# device.net
KiCad netlist of a schematic drawn in Altium Designer
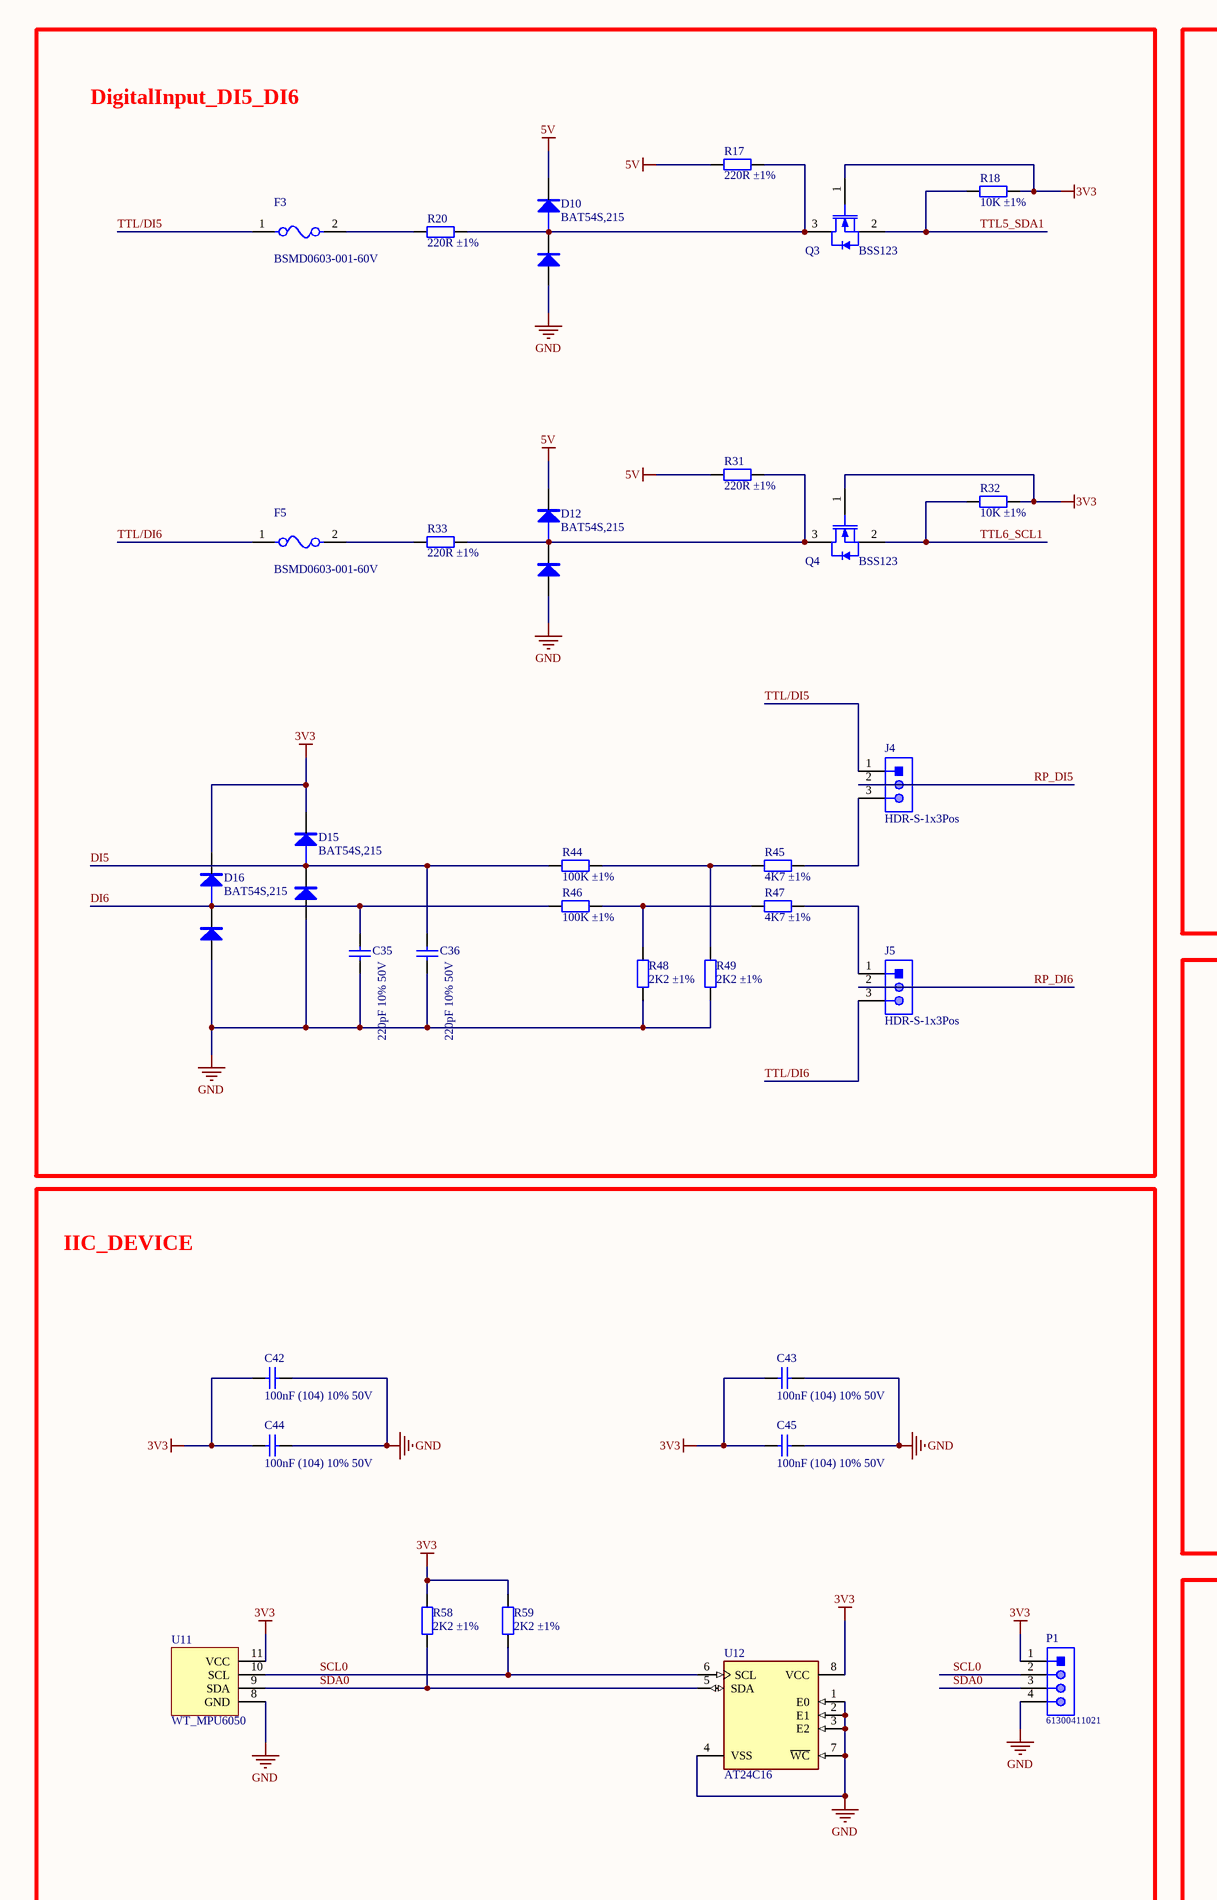
[diagram p0: device.SchDoc, left]
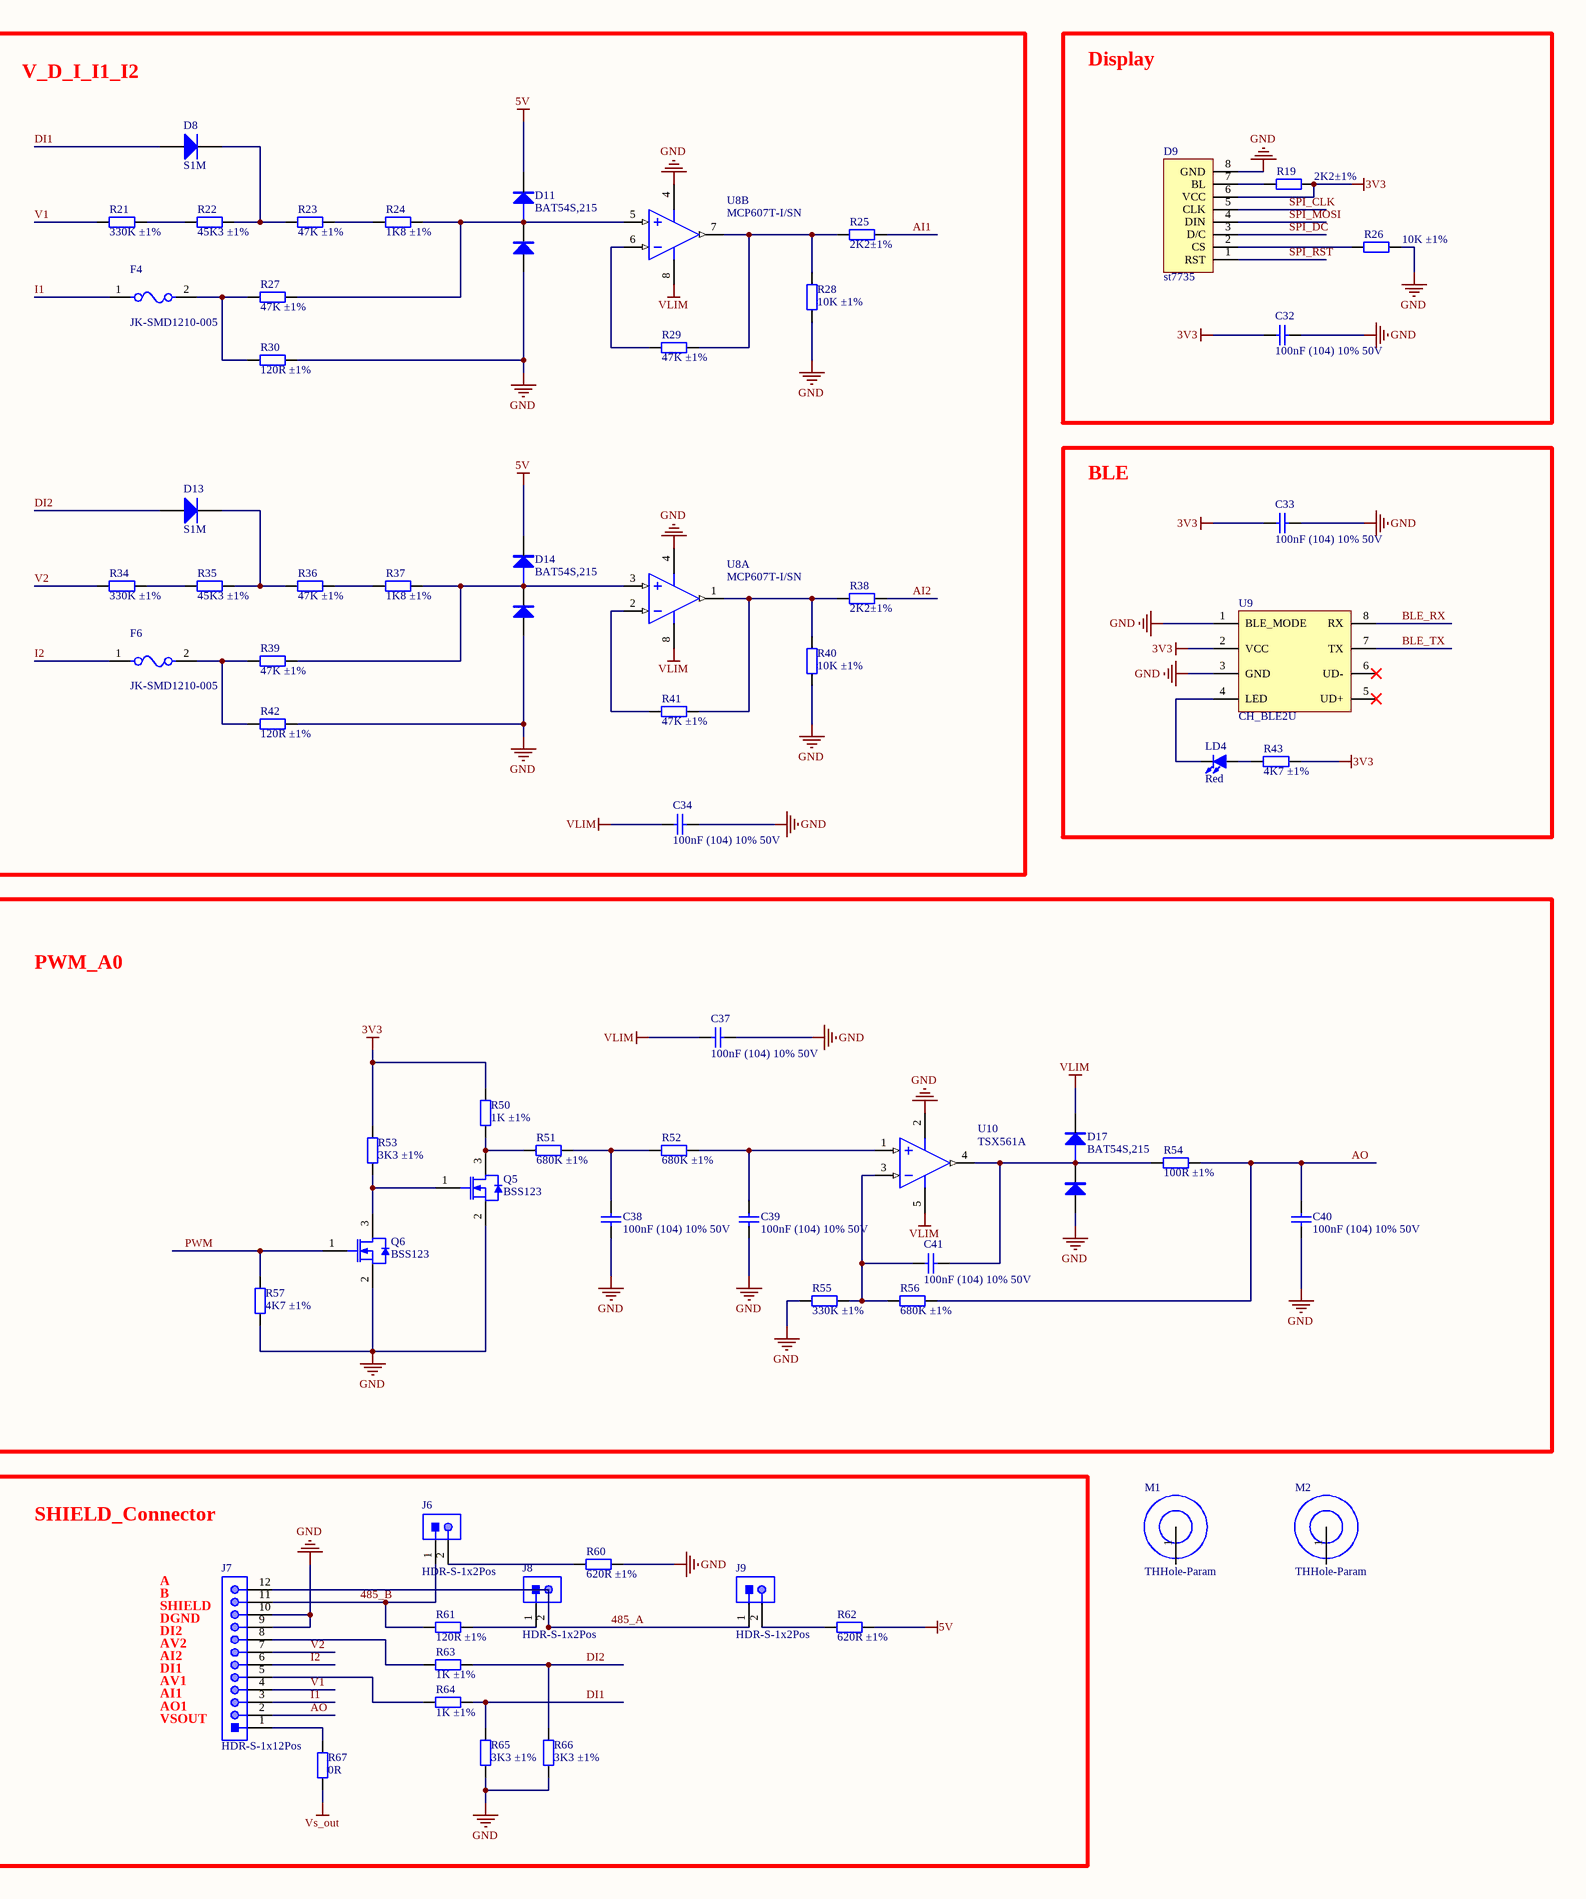
[diagram p1: device.SchDoc, right]

(export (version "E")
  (design (tool "Eeschema 10.0.6"))
  (components
    (comp (ref "C32")
      (value "100nF (104) 10% 50V")
      (footprint "0402_C")
      (description "贴片电容")
      (libsource (lib "aiskylab-02Cap-01Ceramics") (part "0402 100nF (104) 10% 16V"))
    )
    (comp (ref "C33")
      (value "100nF (104) 10% 50V")
      (footprint "0402_C")
      (description "贴片电容")
      (libsource (lib "aiskylab-02Cap-01Ceramics") (part "0402 100nF (104) 10% 16V"))
    )
    (comp (ref "C34")
      (value "100nF (104) 10% 50V")
      (footprint "0402_C")
      (description "贴片电容")
      (libsource (lib "aiskylab-02Cap-01Ceramics") (part "0402 100nF (104) 10% 16V"))
    )
    (comp (ref "C35")
      (value "220pF 10% 50V")
      (footprint "0402_C")
      (description "贴片电容")
      (libsource (lib "aiskylab-02Cap-01Ceramics") (part "0402 150pF (151) 10% 50V"))
    )
    (comp (ref "C36")
      (value "220pF 10% 50V")
      (footprint "0402_C")
      (description "贴片电容")
      (libsource (lib "aiskylab-02Cap-01Ceramics") (part "0402 150pF (151) 10% 50V"))
    )
    (comp (ref "C37")
      (value "100nF (104) 10% 50V")
      (footprint "0402_C")
      (description "贴片电容")
      (libsource (lib "aiskylab-02Cap-01Ceramics") (part "0402 100nF (104) 10% 16V"))
    )
    (comp (ref "C38")
      (value "100nF (104) 10% 50V")
      (footprint "0402_C")
      (description "贴片电容")
      (libsource (lib "aiskylab-02Cap-01Ceramics") (part "0402 100nF (104) 10% 16V"))
    )
    (comp (ref "C39")
      (value "100nF (104) 10% 50V")
      (footprint "0402_C")
      (description "贴片电容")
      (libsource (lib "aiskylab-02Cap-01Ceramics") (part "0402 100nF (104) 10% 16V"))
    )
    (comp (ref "C40")
      (value "100nF (104) 10% 50V")
      (footprint "0402_C")
      (description "贴片电容")
      (libsource (lib "aiskylab-02Cap-01Ceramics") (part "0402 100nF (104) 10% 16V"))
    )
    (comp (ref "C41")
      (value "100nF (104) 10% 50V")
      (footprint "0402_C")
      (description "贴片电容")
      (libsource (lib "aiskylab-02Cap-01Ceramics") (part "0402 100nF (104) 10% 16V"))
    )
    (comp (ref "C42")
      (value "100nF (104) 10% 50V")
      (footprint "0402_C")
      (description "贴片电容")
      (libsource (lib "aiskylab-02Cap-01Ceramics") (part "0402 100nF (104) 10% 16V"))
    )
    (comp (ref "C43")
      (value "100nF (104) 10% 50V")
      (footprint "0402_C")
      (description "贴片电容")
      (libsource (lib "aiskylab-02Cap-01Ceramics") (part "0402 100nF (104) 10% 16V"))
    )
    (comp (ref "C44")
      (value "100nF (104) 10% 50V")
      (footprint "0402_C")
      (description "贴片电容")
      (libsource (lib "aiskylab-02Cap-01Ceramics") (part "0402 100nF (104) 10% 16V"))
    )
    (comp (ref "C45")
      (value "100nF (104) 10% 50V")
      (footprint "0402_C")
      (description "贴片电容")
      (libsource (lib "aiskylab-02Cap-01Ceramics") (part "0402 100nF (104) 10% 16V"))
    )
    (comp (ref "D8")
      (value "S1M")
      (footprint "DO-214AC")
      (description "肖特基二极管")
      (fields (field (name "MANUFACTURER") "MCC") (field (name "MANUFACTURER PART NUMBER") "B5817WS-TP"))
      (libsource (lib "aiskylab-04Dio-1K") (part "B5817WS-TP"))
    )
    (comp (ref "D9")
      (value "st7735")
      (footprint "HX-2.54-F-1x8-V")
      (libsource (lib "Schlib_PICO") (part "st7735"))
    )
    (comp (ref "D10")
      (value "BAT54S,215")
      (footprint "SOT-23-3")
      (description "肖特基二极管")
      (libsource (lib "Schlib1") (part "BAT54S,215"))
    )
    (comp (ref "D11")
      (value "BAT54S,215")
      (footprint "SOT-23-3")
      (description "肖特基二极管")
      (libsource (lib "Schlib1") (part "BAT54S,215"))
    )
    (comp (ref "D12")
      (value "BAT54S,215")
      (footprint "SOT-23-3")
      (description "肖特基二极管")
      (libsource (lib "Schlib1") (part "BAT54S,215"))
    )
    (comp (ref "D13")
      (value "S1M")
      (footprint "DO-214AC")
      (description "肖特基二极管")
      (fields (field (name "MANUFACTURER") "MCC") (field (name "MANUFACTURER PART NUMBER") "B5817WS-TP"))
      (libsource (lib "aiskylab-04Dio-1K") (part "B5817WS-TP"))
    )
    (comp (ref "D14")
      (value "BAT54S,215")
      (footprint "SOT-23-3")
      (description "肖特基二极管")
      (libsource (lib "Schlib1") (part "BAT54S,215"))
    )
    (comp (ref "D15")
      (value "BAT54S,215")
      (footprint "SOT-23-3")
      (description "肖特基二极管")
      (libsource (lib "Schlib1") (part "BAT54S,215"))
    )
    (comp (ref "D16")
      (value "BAT54S,215")
      (footprint "SOT-23-3")
      (description "肖特基二极管")
      (libsource (lib "Schlib1") (part "BAT54S,215"))
    )
    (comp (ref "D17")
      (value "BAT54S,215")
      (footprint "SOT-23-3")
      (description "肖特基二极管")
      (libsource (lib "Schlib1") (part "BAT54S,215"))
    )
    (comp (ref "F3")
      (value "BSMD0603-001-60V")
      (footprint "FU 0805")
      (description "贴片保险，自恢复")
      (libsource (lib "aiskylab-09CirProtect") (part "Fuse 2A 0805"))
    )
    (comp (ref "F4")
      (value "JK-SMD1210-005")
      (footprint "1210_R")
      (description "贴片保险，自恢复")
      (libsource (lib "aiskylab-09CirProtect") (part "Fuse 2A 0805"))
    )
    (comp (ref "F5")
      (value "BSMD0603-001-60V")
      (footprint "FU 0805")
      (description "贴片保险，自恢复")
      (libsource (lib "aiskylab-09CirProtect") (part "Fuse 2A 0805"))
    )
    (comp (ref "F6")
      (value "JK-SMD1210-005")
      (footprint "1210_R")
      (description "贴片保险，自恢复")
      (libsource (lib "aiskylab-09CirProtect") (part "Fuse 2A 0805"))
    )
    (comp (ref "J4")
      (value "HDR-S-1x3Pos")
      (footprint "HX-2.54-F-1x3-V")
      (description "2.54mm 排座")
      (libsource (lib "aiskylab-14Connectors-17HeadersAndWireHousing") (part "HDR-S-1x3Pos"))
    )
    (comp (ref "J5")
      (value "HDR-S-1x3Pos")
      (footprint "HX-2.54-F-1x3-V")
      (description "2.54mm 排座")
      (libsource (lib "aiskylab-14Connectors-17HeadersAndWireHousing") (part "HDR-S-1x3Pos"))
    )
    (comp (ref "J6")
      (value "HDR-S-1x2Pos")
      (footprint "Pin Header 1x2 TH Pitch 2.54mm")
      (description "2.54mm 排座")
      (libsource (lib "aiskylab-14Connectors-17HeadersAndWireHousing") (part "HDR-S-1x2Pos"))
    )
    (comp (ref "J7")
      (value "HDR-S-1x12Pos")
      (footprint "KF2EDGK-2.54-WI-12P")
      (description "2.54mm 排座")
      (libsource (lib "aiskylab-14Connectors-17HeadersAndWireHousing") (part "HDR-S-1x12Pos"))
    )
    (comp (ref "J8")
      (value "HDR-S-1x2Pos")
      (footprint "Pin Header 1x2 TH Pitch 2.54mm")
      (description "2.54mm 排座")
      (libsource (lib "aiskylab-14Connectors-17HeadersAndWireHousing") (part "HDR-S-1x2Pos"))
    )
    (comp (ref "J9")
      (value "HDR-S-1x2Pos")
      (footprint "Pin Header 1x2 TH Pitch 2.54mm")
      (description "2.54mm 排座")
      (libsource (lib "aiskylab-14Connectors-17HeadersAndWireHousing") (part "HDR-S-1x2Pos"))
    )
    (comp (ref "LD4")
      (value "Red")
      (footprint "0603_LED")
      (description "贴片LED")
      (fields (field (name "版权归属") "源创客"))
      (libsource (lib "aiskylab-04Dio-LED") (part "LED"))
    )
    (comp (ref "M1")
      (value "THHole-Param")
      (footprint "MTG300_600")
      (description "金属化可接地固定孔")
      (libsource (lib "aiskylab-14Connectors-20TestAndMechenical") (part "MHole-1"))
    )
    (comp (ref "M2")
      (value "THHole-Param")
      (footprint "MTG300_600")
      (description "金属化可接地固定孔")
      (libsource (lib "aiskylab-14Connectors-20TestAndMechenical") (part "MHole-1"))
    )
    (comp (ref "P1")
      (value "61300411021")
      (footprint "HDR-2.54-1x4-H")
      (description "2.54mm 排针")
      (fields (field (name "MANUFACTURER") "Wurth Elektronik") (field (name "PUBLISHER") "WurthElektronik"))
      (libsource (lib "aiskylab-14Connectors-17HeadersAndWireHousing") (part "HDR-1x4Pos"))
    )
    (comp (ref "Q3")
      (value "BSS123")
      (footprint "SOT95P245X110-3N")
      (description "Trans Mosfet N-ch 60V 0.115A 3-PIN SOT-23 T/r")
      (fields (field (name "MANUFACTURER") "Infineon") (field (name "MANUFACTURER PART NUMBER") "2N7002"))
      (libsource (lib "aiskylab-05Transistors") (part "2N7002"))
    )
    (comp (ref "Q4")
      (value "BSS123")
      (footprint "SOT95P245X110-3N")
      (description "Trans Mosfet N-ch 60V 0.115A 3-PIN SOT-23 T/r")
      (fields (field (name "MANUFACTURER") "Infineon") (field (name "MANUFACTURER PART NUMBER") "2N7002"))
      (libsource (lib "aiskylab-05Transistors") (part "2N7002"))
    )
    (comp (ref "Q5")
      (value "BSS123")
      (footprint "SOT95P245X110-3N")
      (description "Trans Mosfet N-ch 60V 0.115A 3-PIN SOT-23 T/r")
      (fields (field (name "MANUFACTURER") "Infineon") (field (name "MANUFACTURER PART NUMBER") "2N7002"))
      (libsource (lib "aiskylab-05Transistors") (part "2N7002"))
    )
    (comp (ref "Q6")
      (value "BSS123")
      (footprint "SOT95P245X110-3N")
      (description "Trans Mosfet N-ch 60V 0.115A 3-PIN SOT-23 T/r")
      (fields (field (name "MANUFACTURER") "Infineon") (field (name "MANUFACTURER PART NUMBER") "2N7002"))
      (libsource (lib "aiskylab-05Transistors") (part "2N7002"))
    )
    (comp (ref "R17")
      (value "220R ±1%")
      (footprint "0402_R")
      (description "贴片电阻")
      (libsource (lib "aiskylab-01Resistors") (part "0402 1.2KΩ (1201) 1%"))
    )
    (comp (ref "R18")
      (value "10K ±1%")
      (footprint "0402_R")
      (description "贴片电阻")
      (libsource (lib "") (part "0402 1.2KΩ (1201) 1%_1"))
    )
    (comp (ref "R19")
      (value "2K2±1%")
      (footprint "0402_R")
      (description "贴片电阻")
      (libsource (lib "aiskylab-01Resistors") (part "0402 1.2KΩ (1201) 1%"))
    )
    (comp (ref "R20")
      (value "220R ±1%")
      (footprint "0402_R")
      (description "贴片电阻")
      (libsource (lib "aiskylab-01Resistors") (part "0402 1.2KΩ (1201) 1%"))
    )
    (comp (ref "R21")
      (value "330K ±1%")
      (footprint "0402_R")
      (description "贴片电阻")
      (libsource (lib "") (part "0402 1.2KΩ (1201) 1%_1"))
    )
    (comp (ref "R22")
      (value "45K3 ±1%")
      (footprint "0402_R")
      (description "贴片电阻")
      (libsource (lib "") (part "0402 1.2KΩ (1201) 1%_1"))
    )
    (comp (ref "R23")
      (value "47K ±1%")
      (footprint "0402_R")
      (description "贴片电阻")
      (libsource (lib "") (part "0402 1.2KΩ (1201) 1%_1"))
    )
    (comp (ref "R24")
      (value "1K8 ±1%")
      (footprint "0402_R")
      (description "贴片电阻")
      (libsource (lib "") (part "0402 1.2KΩ (1201) 1%_1"))
    )
    (comp (ref "R25")
      (value "2K2±1%")
      (footprint "0402_R")
      (description "贴片电阻")
      (libsource (lib "aiskylab-01Resistors") (part "0402 1.2KΩ (1201) 1%"))
    )
    (comp (ref "R26")
      (value "10K ±1%")
      (footprint "0402_R")
      (description "贴片电阻")
      (libsource (lib "aiskylab-01Resistors") (part "0402 1.2KΩ (1201) 1%"))
    )
    (comp (ref "R27")
      (value "47K ±1%")
      (footprint "0402_R")
      (description "贴片电阻")
      (libsource (lib "") (part "0402 1.2KΩ (1201) 1%_1"))
    )
    (comp (ref "R28")
      (value "10K ±1%")
      (footprint "0402_R")
      (description "贴片电阻")
      (libsource (lib "") (part "0402 1.2KΩ (1201) 1%_2"))
    )
    (comp (ref "R29")
      (value "47K ±1%")
      (footprint "0402_R")
      (description "贴片电阻")
      (libsource (lib "") (part "0402 1.2KΩ (1201) 1%_1"))
    )
    (comp (ref "R30")
      (value "120R ±1%")
      (footprint "RS 1/4W-V3")
      (description "贴片电阻")
      (libsource (lib "") (part "0402 1.2KΩ (1201) 1%_1"))
    )
    (comp (ref "R31")
      (value "220R ±1%")
      (footprint "0402_R")
      (description "贴片电阻")
      (libsource (lib "aiskylab-01Resistors") (part "0402 1.2KΩ (1201) 1%"))
    )
    (comp (ref "R32")
      (value "10K ±1%")
      (footprint "0402_R")
      (description "贴片电阻")
      (libsource (lib "") (part "0402 1.2KΩ (1201) 1%_1"))
    )
    (comp (ref "R33")
      (value "220R ±1%")
      (footprint "0402_R")
      (description "贴片电阻")
      (libsource (lib "aiskylab-01Resistors") (part "0402 1.2KΩ (1201) 1%"))
    )
    (comp (ref "R34")
      (value "330K ±1%")
      (footprint "0402_R")
      (description "贴片电阻")
      (libsource (lib "") (part "0402 1.2KΩ (1201) 1%_1"))
    )
    (comp (ref "R35")
      (value "45K3 ±1%")
      (footprint "0402_R")
      (description "贴片电阻")
      (libsource (lib "") (part "0402 1.2KΩ (1201) 1%_1"))
    )
    (comp (ref "R36")
      (value "47K ±1%")
      (footprint "0402_R")
      (description "贴片电阻")
      (libsource (lib "") (part "0402 1.2KΩ (1201) 1%_1"))
    )
    (comp (ref "R37")
      (value "1K8 ±1%")
      (footprint "0402_R")
      (description "贴片电阻")
      (libsource (lib "") (part "0402 1.2KΩ (1201) 1%_1"))
    )
    (comp (ref "R38")
      (value "2K2±1%")
      (footprint "0402_R")
      (description "贴片电阻")
      (libsource (lib "aiskylab-01Resistors") (part "0402 1.2KΩ (1201) 1%"))
    )
    (comp (ref "R39")
      (value "47K ±1%")
      (footprint "0402_R")
      (description "贴片电阻")
      (libsource (lib "") (part "0402 1.2KΩ (1201) 1%_1"))
    )
    (comp (ref "R40")
      (value "10K ±1%")
      (footprint "0402_R")
      (description "贴片电阻")
      (libsource (lib "") (part "0402 1.2KΩ (1201) 1%_2"))
    )
    (comp (ref "R41")
      (value "47K ±1%")
      (footprint "0402_R")
      (description "贴片电阻")
      (libsource (lib "") (part "0402 1.2KΩ (1201) 1%_1"))
    )
    (comp (ref "R42")
      (value "120R ±1%")
      (footprint "RS 1/4W-V3")
      (description "贴片电阻")
      (libsource (lib "") (part "0402 1.2KΩ (1201) 1%_1"))
    )
    (comp (ref "R43")
      (value "4K7 ±1%")
      (footprint "0402_R")
      (description "贴片电阻")
      (libsource (lib "aiskylab-01Resistors") (part "0402 100KΩ (1003) 1%"))
    )
    (comp (ref "R44")
      (value "100K ±1%")
      (footprint "0402_R")
      (description "贴片电阻")
      (libsource (lib "aiskylab-01Resistors") (part "0402 1.2KΩ (1201) 1%"))
    )
    (comp (ref "R45")
      (value "4K7 ±1%")
      (footprint "0402_R")
      (description "贴片电阻")
      (libsource (lib "aiskylab-01Resistors") (part "0402 1.2KΩ (1201) 1%"))
    )
    (comp (ref "R46")
      (value "100K ±1%")
      (footprint "0402_R")
      (description "贴片电阻")
      (libsource (lib "aiskylab-01Resistors") (part "0402 1.2KΩ (1201) 1%"))
    )
    (comp (ref "R47")
      (value "4K7 ±1%")
      (footprint "0402_R")
      (description "贴片电阻")
      (libsource (lib "aiskylab-01Resistors") (part "0402 1.2KΩ (1201) 1%"))
    )
    (comp (ref "R48")
      (value "2K2 ±1%")
      (footprint "0402_R")
      (description "贴片电阻")
      (libsource (lib "") (part "0402 1.2KΩ (1201) 1%_2"))
    )
    (comp (ref "R49")
      (value "2K2 ±1%")
      (footprint "0402_R")
      (description "贴片电阻")
      (libsource (lib "") (part "0402 1.2KΩ (1201) 1%_2"))
    )
    (comp (ref "R50")
      (value "1K ±1%")
      (footprint "0402_R")
      (description "贴片电阻")
      (libsource (lib "") (part "0402 1.2KΩ (1201) 1%_2"))
    )
    (comp (ref "R51")
      (value "680K ±1%")
      (footprint "0402_R")
      (description "贴片电阻")
      (libsource (lib "aiskylab-01Resistors") (part "0402 1.2KΩ (1201) 1%"))
    )
    (comp (ref "R52")
      (value "680K ±1%")
      (footprint "0402_R")
      (description "贴片电阻")
      (libsource (lib "aiskylab-01Resistors") (part "0402 1.2KΩ (1201) 1%"))
    )
    (comp (ref "R53")
      (value "3K3 ±1%")
      (footprint "0402_R")
      (description "贴片电阻")
      (libsource (lib "") (part "0402 1.2KΩ (1201) 1%_2"))
    )
    (comp (ref "R54")
      (value "100R ±1%")
      (footprint "0603_R")
      (description "贴片电阻")
      (libsource (lib "aiskylab-01Resistors") (part "0402 1.2KΩ (1201) 1%"))
    )
    (comp (ref "R55")
      (value "330K ±1%")
      (footprint "0603_R")
      (description "贴片电阻")
      (libsource (lib "aiskylab-01Resistors") (part "0402 1.2KΩ (1201) 1%"))
    )
    (comp (ref "R56")
      (value "680K ±1%")
      (footprint "0603_R")
      (description "贴片电阻")
      (libsource (lib "aiskylab-01Resistors") (part "0402 1.2KΩ (1201) 1%"))
    )
    (comp (ref "R57")
      (value "4K7 ±1%")
      (footprint "0402_R")
      (description "贴片电阻")
      (libsource (lib "") (part "0402 1.2KΩ (1201) 1%_2"))
    )
    (comp (ref "R58")
      (value "2K2 ±1%")
      (footprint "0402_R")
      (description "贴片电阻")
      (libsource (lib "") (part "0402 1.2KΩ (1201) 1%_2"))
    )
    (comp (ref "R59")
      (value "2K2 ±1%")
      (footprint "0402_R")
      (description "贴片电阻")
      (libsource (lib "") (part "0402 1.2KΩ (1201) 1%_2"))
    )
    (comp (ref "R60")
      (value "620R ±1%")
      (footprint "0603_R")
      (description "贴片电阻")
      (libsource (lib "aiskylab-01Resistors") (part "0402 1.2KΩ (1201) 1%"))
    )
    (comp (ref "R61")
      (value "120R ±1%")
      (footprint "0603_R")
      (description "贴片电阻")
      (libsource (lib "aiskylab-01Resistors") (part "0402 1.2KΩ (1201) 1%"))
    )
    (comp (ref "R62")
      (value "620R ±1%")
      (footprint "0603_R")
      (description "贴片电阻")
      (libsource (lib "aiskylab-01Resistors") (part "0402 1.2KΩ (1201) 1%"))
    )
    (comp (ref "R63")
      (value "1K ±1%")
      (footprint "0402_R")
      (description "贴片电阻")
      (libsource (lib "aiskylab-01Resistors") (part "0402 1.2KΩ (1201) 1%"))
    )
    (comp (ref "R64")
      (value "1K ±1%")
      (footprint "0402_R")
      (description "贴片电阻")
      (libsource (lib "aiskylab-01Resistors") (part "0402 1.2KΩ (1201) 1%"))
    )
    (comp (ref "R65")
      (value "3K3 ±1%")
      (footprint "0402_R")
      (description "贴片电阻")
      (libsource (lib "") (part "0402 1.2KΩ (1201) 1%_3"))
    )
    (comp (ref "R66")
      (value "3K3 ±1%")
      (footprint "0402_R")
      (description "贴片电阻")
      (libsource (lib "") (part "0402 1.2KΩ (1201) 1%_3"))
    )
    (comp (ref "R67")
      (value "0R")
      (footprint "1210_R")
      (description "贴片电阻")
      (libsource (lib "") (part "0402 1.2KΩ (1201) 1%_3"))
    )
    (comp (ref "U8")
      (value "MCP607T-I/SN")
      (footprint "D0008A_L")
      (libsource (lib "aiskylab-06IC-01Linear") (part "TI-LM358DR"))
    )
    (comp (ref "U9")
      (value "CH_BLE2U")
      (footprint "CH_BLE2U")
      (description "BLE模块")
      (libsource (lib "Schlib1") (part "CH_BLE2U"))
    )
    (comp (ref "U10") (value "TSX561A") (footprint "SOT-23-5") (libsource (lib "Schlib1") (part "TSX561A")))
    (comp (ref "U11")
      (value "WT_MPU6050")
      (footprint "WT_MPU6050")
      (libsource (lib "Schlib1") (part "WT_MPU6050"))
    )
    (comp (ref "U12")
      (value "AT24C16")
      (footprint "FP-SO8N-SO-A-IPC_A")
      (description "IC EEPROM 2K I2C 400KHZ 8SO")
      (fields
        (field (name "MANUFACTURER") "STMicroelectronics")
        (field (name "MANUFACTURER PART NUMBER") "M24C02-WMN6TP")
      )
      (libsource (lib "aiskylab-06IC-02Memory") (part "ST-M24C02-WMN6TP"))
    )
  )
  (nets
    (net (code "1") (name "/485_A") (class "Default")
      (node (ref "J7") (pin "12") (pinfunction "12_12") (pintype "passive"))
      (node (ref "J8") (pin "2") (pinfunction "2_2") (pintype "passive"))
      (node (ref "J9") (pin "1") (pinfunction "1_1") (pintype "passive"))
    )
    (net (code "2") (name "/485_B") (class "Default")
      (node (ref "J6") (pin "1") (pinfunction "1_1") (pintype "passive"))
      (node (ref "J7") (pin "11") (pinfunction "11_11") (pintype "passive"))
      (node (ref "R61") (pin "1") (pinfunction "1_1") (pintype "passive"))
    )
    (net (code "3") (name "/AI1") (class "Default")
      (node (ref "R25") (pin "2") (pinfunction "2_2") (pintype "passive"))
    )
    (net (code "4") (name "/AI2") (class "Default")
      (node (ref "R38") (pin "2") (pinfunction "2_2") (pintype "passive"))
    )
    (net (code "5") (name "/AO") (class "Default")
      (node (ref "C40") (pin "1") (pinfunction "1_1") (pintype "passive"))
      (node (ref "J7") (pin "2") (pinfunction "2_2") (pintype "passive"))
      (node (ref "R54") (pin "2") (pinfunction "2_2") (pintype "passive"))
      (node (ref "R56") (pin "2") (pinfunction "2_2") (pintype "passive"))
    )
    (net (code "6") (name "/BLE_RX") (class "Default")
      (node (ref "U9") (pin "8") (pinfunction "RX_8") (pintype "passive"))
    )
    (net (code "7") (name "/BLE_TX") (class "Default")
      (node (ref "U9") (pin "7") (pinfunction "TX_7") (pintype "passive"))
    )
    (net (code "8") (name "/DI1") (class "Default")
      (node (ref "D8") (pin "2") (pinfunction "A_2") (pintype "passive"))
      (node (ref "R64") (pin "2") (pinfunction "2_2") (pintype "passive"))
      (node (ref "R65") (pin "2") (pinfunction "2_2") (pintype "passive"))
    )
    (net (code "9") (name "/DI2") (class "Default")
      (node (ref "D13") (pin "2") (pinfunction "A_2") (pintype "passive"))
      (node (ref "R63") (pin "2") (pinfunction "2_2") (pintype "passive"))
      (node (ref "R66") (pin "2") (pinfunction "2_2") (pintype "passive"))
    )
    (net (code "10") (name "/DI5") (class "Default")
      (node (ref "C36") (pin "2") (pinfunction "2_2") (pintype "passive"))
      (node (ref "D15") (pin "3") (pinfunction "3_3") (pintype "passive"))
      (node (ref "R44") (pin "1") (pinfunction "1_1") (pintype "passive"))
    )
    (net (code "11") (name "/DI6") (class "Default")
      (node (ref "C35") (pin "2") (pinfunction "2_2") (pintype "passive"))
      (node (ref "D16") (pin "3") (pinfunction "3_3") (pintype "passive"))
      (node (ref "R46") (pin "1") (pinfunction "1_1") (pintype "passive"))
    )
    (net (code "12") (name "/I1") (class "Default")
      (node (ref "F4") (pin "1") (pinfunction "1_1") (pintype "passive"))
      (node (ref "J7") (pin "3") (pinfunction "3_3") (pintype "passive"))
    )
    (net (code "13") (name "/I2") (class "Default")
      (node (ref "F6") (pin "1") (pinfunction "1_1") (pintype "passive"))
      (node (ref "J7") (pin "6") (pinfunction "6_6") (pintype "passive"))
    )
    (net (code "14") (name "/PWM") (class "Default")
      (node (ref "Q6") (pin "1") (pinfunction "GATE_1") (pintype "passive"))
      (node (ref "R57") (pin "1") (pinfunction "1_1") (pintype "passive"))
    )
    (net (code "15") (name "/RP_DI5") (class "Default")
      (node (ref "J4") (pin "2") (pinfunction "2_2") (pintype "passive"))
    )
    (net (code "16") (name "/RP_DI6") (class "Default")
      (node (ref "J5") (pin "2") (pinfunction "2_2") (pintype "passive"))
    )
    (net (code "17") (name "/SCL0") (class "Default")
      (node (ref "P1") (pin "2") (pinfunction "2_2") (pintype "passive"))
      (node (ref "R59") (pin "2") (pinfunction "2_2") (pintype "passive"))
      (node (ref "U11") (pin "10") (pinfunction "SCL_10") (pintype "passive"))
      (node (ref "U12") (pin "6") (pinfunction "SCL_6") (pintype "input"))
    )
    (net (code "18") (name "/SDA0") (class "Default")
      (node (ref "P1") (pin "3") (pinfunction "3_3") (pintype "passive"))
      (node (ref "R58") (pin "2") (pinfunction "2_2") (pintype "passive"))
      (node (ref "U11") (pin "9") (pinfunction "SDA_9") (pintype "passive"))
      (node (ref "U12") (pin "5") (pinfunction "SDA_5") (pintype "bidirectional"))
    )
    (net (code "19") (name "/SPI_CLK") (class "Default")
      (node (ref "D9") (pin "5") (pinfunction "CLK_5") (pintype "passive"))
    )
    (net (code "20") (name "/SPI_DC") (class "Default")
      (node (ref "D9") (pin "3") (pinfunction "D/C_3") (pintype "passive"))
    )
    (net (code "21") (name "/SPI_MOSI") (class "Default")
      (node (ref "D9") (pin "4") (pinfunction "DIN_4") (pintype "passive"))
    )
    (net (code "22") (name "/SPI_RST") (class "Default")
      (node (ref "D9") (pin "1") (pinfunction "RST_1") (pintype "passive"))
    )
    (net (code "23") (name "/TTL5_SDA1") (class "Default")
      (node (ref "Q3") (pin "2") (pinfunction "SOURCE_2") (pintype "passive"))
      (node (ref "R18") (pin "2") (pinfunction "2_2") (pintype "passive"))
    )
    (net (code "24") (name "/TTL6_SCL1") (class "Default")
      (node (ref "Q4") (pin "2") (pinfunction "SOURCE_2") (pintype "passive"))
      (node (ref "R32") (pin "2") (pinfunction "2_2") (pintype "passive"))
    )
    (net (code "25") (name "/TTL{slash}DI5") (class "Default")
      (node (ref "F3") (pin "1") (pinfunction "1_1") (pintype "passive"))
      (node (ref "J4") (pin "1") (pinfunction "1_1") (pintype "passive"))
    )
    (net (code "26") (name "/TTL{slash}DI6") (class "Default")
      (node (ref "F5") (pin "1") (pinfunction "1_1") (pintype "passive"))
      (node (ref "J5") (pin "3") (pinfunction "3_3") (pintype "passive"))
    )
    (net (code "27") (name "/V1") (class "Default")
      (node (ref "J7") (pin "4") (pinfunction "4_4") (pintype "passive"))
      (node (ref "R21") (pin "2") (pinfunction "2_2") (pintype "passive"))
    )
    (net (code "28") (name "/V2") (class "Default")
      (node (ref "J7") (pin "7") (pinfunction "7_7") (pintype "passive"))
      (node (ref "R34") (pin "2") (pinfunction "2_2") (pintype "passive"))
    )
    (net (code "29") (name "3V3") (class "Default")
      (node (ref "C32") (pin "1") (pinfunction "1_1") (pintype "passive"))
      (node (ref "C33") (pin "1") (pinfunction "1_1") (pintype "passive"))
      (node (ref "C42") (pin "1") (pinfunction "1_1") (pintype "passive"))
      (node (ref "C43") (pin "1") (pinfunction "1_1") (pintype "passive"))
      (node (ref "C44") (pin "1") (pinfunction "1_1") (pintype "passive"))
      (node (ref "C45") (pin "1") (pinfunction "1_1") (pintype "passive"))
      (node (ref "D15") (pin "2") (pinfunction "2_2") (pintype "passive"))
      (node (ref "D16") (pin "2") (pinfunction "2_2") (pintype "passive"))
      (node (ref "D9") (pin "6") (pinfunction "VCC_6") (pintype "passive"))
      (node (ref "P1") (pin "1") (pinfunction "1_1") (pintype "passive"))
      (node (ref "Q3") (pin "1") (pinfunction "GATE_1") (pintype "passive"))
      (node (ref "Q4") (pin "1") (pinfunction "GATE_1") (pintype "passive"))
      (node (ref "R18") (pin "1") (pinfunction "1_1") (pintype "passive"))
      (node (ref "R19") (pin "2") (pinfunction "2_2") (pintype "passive"))
      (node (ref "R32") (pin "1") (pinfunction "1_1") (pintype "passive"))
      (node (ref "R43") (pin "2") (pinfunction "2_2") (pintype "passive"))
      (node (ref "R50") (pin "1") (pinfunction "1_1") (pintype "passive"))
      (node (ref "R53") (pin "1") (pinfunction "1_1") (pintype "passive"))
      (node (ref "R58") (pin "1") (pinfunction "1_1") (pintype "passive"))
      (node (ref "R59") (pin "1") (pinfunction "1_1") (pintype "passive"))
      (node (ref "U11") (pin "11") (pinfunction "VCC_11") (pintype "passive"))
      (node (ref "U12") (pin "8") (pinfunction "VCC_8") (pintype "power_in"))
      (node (ref "U9") (pin "2") (pinfunction "VCC_2") (pintype "passive"))
    )
    (net (code "30") (name "5V") (class "Default")
      (node (ref "D10") (pin "2") (pinfunction "2_2") (pintype "passive"))
      (node (ref "D11") (pin "2") (pinfunction "2_2") (pintype "passive"))
      (node (ref "D12") (pin "2") (pinfunction "2_2") (pintype "passive"))
      (node (ref "D14") (pin "2") (pinfunction "2_2") (pintype "passive"))
      (node (ref "R17") (pin "1") (pinfunction "1_1") (pintype "passive"))
      (node (ref "R31") (pin "1") (pinfunction "1_1") (pintype "passive"))
      (node (ref "R62") (pin "2") (pinfunction "2_2") (pintype "passive"))
    )
    (net (code "31") (name "GND") (class "Default")
      (node (ref "C32") (pin "2") (pinfunction "2_2") (pintype "passive"))
      (node (ref "C33") (pin "2") (pinfunction "2_2") (pintype "passive"))
      (node (ref "C34") (pin "2") (pinfunction "2_2") (pintype "passive"))
      (node (ref "C35") (pin "1") (pinfunction "1_1") (pintype "passive"))
      (node (ref "C36") (pin "1") (pinfunction "1_1") (pintype "passive"))
      (node (ref "C37") (pin "2") (pinfunction "2_2") (pintype "passive"))
      (node (ref "C38") (pin "1") (pinfunction "1_1") (pintype "passive"))
      (node (ref "C39") (pin "1") (pinfunction "1_1") (pintype "passive"))
      (node (ref "C40") (pin "2") (pinfunction "2_2") (pintype "passive"))
      (node (ref "C42") (pin "2") (pinfunction "2_2") (pintype "passive"))
      (node (ref "C43") (pin "2") (pinfunction "2_2") (pintype "passive"))
      (node (ref "C44") (pin "2") (pinfunction "2_2") (pintype "passive"))
      (node (ref "C45") (pin "2") (pinfunction "2_2") (pintype "passive"))
      (node (ref "D10") (pin "1") (pinfunction "1_1") (pintype "passive"))
      (node (ref "D11") (pin "1") (pinfunction "1_1") (pintype "passive"))
      (node (ref "D12") (pin "1") (pinfunction "1_1") (pintype "passive"))
      (node (ref "D14") (pin "1") (pinfunction "1_1") (pintype "passive"))
      (node (ref "D15") (pin "1") (pinfunction "1_1") (pintype "passive"))
      (node (ref "D16") (pin "1") (pinfunction "1_1") (pintype "passive"))
      (node (ref "D17") (pin "1") (pinfunction "1_1") (pintype "passive"))
      (node (ref "D9") (pin "8") (pinfunction "GND_8") (pintype "passive"))
      (node (ref "J7") (pin "10") (pinfunction "10_10") (pintype "passive"))
      (node (ref "J7") (pin "9") (pinfunction "9_9") (pintype "passive"))
      (node (ref "P1") (pin "4") (pinfunction "4_4") (pintype "passive"))
      (node (ref "Q5") (pin "2") (pinfunction "SOURCE_2") (pintype "passive"))
      (node (ref "Q6") (pin "2") (pinfunction "SOURCE_2") (pintype "passive"))
      (node (ref "R26") (pin "2") (pinfunction "2_2") (pintype "passive"))
      (node (ref "R28") (pin "2") (pinfunction "2_2") (pintype "passive"))
      (node (ref "R30") (pin "1") (pinfunction "1_1") (pintype "passive"))
      (node (ref "R40") (pin "2") (pinfunction "2_2") (pintype "passive"))
      (node (ref "R42") (pin "1") (pinfunction "1_1") (pintype "passive"))
      (node (ref "R48") (pin "2") (pinfunction "2_2") (pintype "passive"))
      (node (ref "R49") (pin "2") (pinfunction "2_2") (pintype "passive"))
      (node (ref "R55") (pin "1") (pinfunction "1_1") (pintype "passive"))
      (node (ref "R57") (pin "2") (pinfunction "2_2") (pintype "passive"))
      (node (ref "R60") (pin "2") (pinfunction "2_2") (pintype "passive"))
      (node (ref "R65") (pin "1") (pinfunction "1_1") (pintype "passive"))
      (node (ref "R66") (pin "1") (pinfunction "1_1") (pintype "passive"))
      (node (ref "U10") (pin "2") (pinfunction "GND_2") (pintype "power_in"))
      (node (ref "U11") (pin "8") (pinfunction "GND_8") (pintype "passive"))
      (node (ref "U12") (pin "1") (pinfunction "E0_1") (pintype "input"))
      (node (ref "U12") (pin "2") (pinfunction "E1_2") (pintype "input"))
      (node (ref "U12") (pin "3") (pinfunction "E2_3") (pintype "input"))
      (node (ref "U12") (pin "4") (pinfunction "VSS_4") (pintype "power_in"))
      (node (ref "U12") (pin "7") (pinfunction "~{WC}_7") (pintype "input"))
      (node (ref "U8") (pin "4") (pinfunction "GND_4") (pintype "power_in"))
      (node (ref "U9") (pin "1") (pinfunction "BLE_MODE_1") (pintype "passive"))
      (node (ref "U9") (pin "3") (pinfunction "GND_3") (pintype "passive"))
    )
    (net (code "32") (name "Net-(C38-Pad2)") (class "Default")
      (node (ref "C38") (pin "2") (pinfunction "2_2") (pintype "passive"))
      (node (ref "R51") (pin "2") (pinfunction "2_2") (pintype "passive"))
      (node (ref "R52") (pin "1") (pinfunction "1_1") (pintype "passive"))
    )
    (net (code "33") (name "Net-(D8-K)") (class "Default")
      (node (ref "D8") (pin "1") (pinfunction "K_1") (pintype "passive"))
      (node (ref "R22") (pin "1") (pinfunction "1_1") (pintype "passive"))
      (node (ref "R23") (pin "2") (pinfunction "2_2") (pintype "passive"))
    )
    (net (code "34") (name "Net-(D9-BL)") (class "Default")
      (node (ref "D9") (pin "7") (pinfunction "BL_7") (pintype "passive"))
      (node (ref "R19") (pin "1") (pinfunction "1_1") (pintype "passive"))
    )
    (net (code "35") (name "Net-(D9-CS)") (class "Default")
      (node (ref "D9") (pin "2") (pinfunction "CS_2") (pintype "passive"))
      (node (ref "R26") (pin "1") (pinfunction "1_1") (pintype "passive"))
    )
    (net (code "36") (name "Net-(D13-K)") (class "Default")
      (node (ref "D13") (pin "1") (pinfunction "K_1") (pintype "passive"))
      (node (ref "R35") (pin "1") (pinfunction "1_1") (pintype "passive"))
      (node (ref "R36") (pin "2") (pinfunction "2_2") (pintype "passive"))
    )
    (net (code "37") (name "Net-(F3-Pad2)") (class "Default")
      (node (ref "F3") (pin "2") (pinfunction "2_2") (pintype "passive"))
      (node (ref "R20") (pin "1") (pinfunction "1_1") (pintype "passive"))
    )
    (net (code "38") (name "Net-(F4-Pad2)") (class "Default")
      (node (ref "F4") (pin "2") (pinfunction "2_2") (pintype "passive"))
      (node (ref "R27") (pin "2") (pinfunction "2_2") (pintype "passive"))
      (node (ref "R30") (pin "2") (pinfunction "2_2") (pintype "passive"))
    )
    (net (code "39") (name "Net-(F5-Pad2)") (class "Default")
      (node (ref "F5") (pin "2") (pinfunction "2_2") (pintype "passive"))
      (node (ref "R33") (pin "1") (pinfunction "1_1") (pintype "passive"))
    )
    (net (code "40") (name "Net-(F6-Pad2)") (class "Default")
      (node (ref "F6") (pin "2") (pinfunction "2_2") (pintype "passive"))
      (node (ref "R39") (pin "2") (pinfunction "2_2") (pintype "passive"))
      (node (ref "R42") (pin "2") (pinfunction "2_2") (pintype "passive"))
    )
    (net (code "41") (name "Net-(J4-Pad3)") (class "Default")
      (node (ref "J4") (pin "3") (pinfunction "3_3") (pintype "passive"))
      (node (ref "R45") (pin "2") (pinfunction "2_2") (pintype "passive"))
    )
    (net (code "42") (name "Net-(J5-Pad1)") (class "Default")
      (node (ref "J5") (pin "1") (pinfunction "1_1") (pintype "passive"))
      (node (ref "R47") (pin "2") (pinfunction "2_2") (pintype "passive"))
    )
    (net (code "43") (name "Net-(J6-Pad2)") (class "Default")
      (node (ref "J6") (pin "2") (pinfunction "2_2") (pintype "passive"))
      (node (ref "R60") (pin "1") (pinfunction "1_1") (pintype "passive"))
    )
    (net (code "44") (name "Net-(J7-Pad1)") (class "Default")
      (node (ref "J7") (pin "1") (pinfunction "1_1") (pintype "passive"))
      (node (ref "R67") (pin "2") (pinfunction "2_2") (pintype "passive"))
    )
    (net (code "45") (name "Net-(J7-Pad5)") (class "Default")
      (node (ref "J7") (pin "5") (pinfunction "5_5") (pintype "passive"))
      (node (ref "R64") (pin "1") (pinfunction "1_1") (pintype "passive"))
    )
    (net (code "46") (name "Net-(J7-Pad8)") (class "Default")
      (node (ref "J7") (pin "8") (pinfunction "8_8") (pintype "passive"))
      (node (ref "R63") (pin "1") (pinfunction "1_1") (pintype "passive"))
    )
    (net (code "47") (name "Net-(J8-Pad1)") (class "Default")
      (node (ref "J8") (pin "1") (pinfunction "1_1") (pintype "passive"))
      (node (ref "R61") (pin "2") (pinfunction "2_2") (pintype "passive"))
    )
    (net (code "48") (name "Net-(J9-Pad2)") (class "Default")
      (node (ref "J9") (pin "2") (pinfunction "2_2") (pintype "passive"))
      (node (ref "R62") (pin "1") (pinfunction "1_1") (pintype "passive"))
    )
    (net (code "49") (name "Net-(LD4-A)") (class "Default")
      (node (ref "LD4") (pin "1") (pinfunction "A_1") (pintype "passive"))
      (node (ref "R43") (pin "1") (pinfunction "1_1") (pintype "passive"))
    )
    (net (code "50") (name "Net-(LD4-K)") (class "Default")
      (node (ref "LD4") (pin "2") (pinfunction "K_2") (pintype "passive"))
      (node (ref "U9") (pin "4") (pinfunction "LED_4") (pintype "passive"))
    )
    (net (code "51") (name "Net-(Q3-DRAIN)") (class "Default")
      (node (ref "D10") (pin "3") (pinfunction "3_3") (pintype "passive"))
      (node (ref "Q3") (pin "3") (pinfunction "DRAIN_3") (pintype "passive"))
      (node (ref "R17") (pin "2") (pinfunction "2_2") (pintype "passive"))
      (node (ref "R20") (pin "2") (pinfunction "2_2") (pintype "passive"))
    )
    (net (code "52") (name "Net-(Q4-DRAIN)") (class "Default")
      (node (ref "D12") (pin "3") (pinfunction "3_3") (pintype "passive"))
      (node (ref "Q4") (pin "3") (pinfunction "DRAIN_3") (pintype "passive"))
      (node (ref "R31") (pin "2") (pinfunction "2_2") (pintype "passive"))
      (node (ref "R33") (pin "2") (pinfunction "2_2") (pintype "passive"))
    )
    (net (code "53") (name "Net-(Q5-DRAIN)") (class "Default")
      (node (ref "Q5") (pin "3") (pinfunction "DRAIN_3") (pintype "passive"))
      (node (ref "R50") (pin "2") (pinfunction "2_2") (pintype "passive"))
      (node (ref "R51") (pin "1") (pinfunction "1_1") (pintype "passive"))
    )
    (net (code "54") (name "Net-(Q5-GATE)") (class "Default")
      (node (ref "Q5") (pin "1") (pinfunction "GATE_1") (pintype "passive"))
      (node (ref "Q6") (pin "3") (pinfunction "DRAIN_3") (pintype "passive"))
      (node (ref "R53") (pin "2") (pinfunction "2_2") (pintype "passive"))
    )
    (net (code "55") (name "Net-(R21-Pad1)") (class "Default")
      (node (ref "R21") (pin "1") (pinfunction "1_1") (pintype "passive"))
      (node (ref "R22") (pin "2") (pinfunction "2_2") (pintype "passive"))
    )
    (net (code "56") (name "Net-(R23-Pad1)") (class "Default")
      (node (ref "R23") (pin "1") (pinfunction "1_1") (pintype "passive"))
      (node (ref "R24") (pin "2") (pinfunction "2_2") (pintype "passive"))
    )
    (net (code "57") (name "Net-(R34-Pad1)") (class "Default")
      (node (ref "R34") (pin "1") (pinfunction "1_1") (pintype "passive"))
      (node (ref "R35") (pin "2") (pinfunction "2_2") (pintype "passive"))
    )
    (net (code "58") (name "Net-(R36-Pad1)") (class "Default")
      (node (ref "R36") (pin "1") (pinfunction "1_1") (pintype "passive"))
      (node (ref "R37") (pin "2") (pinfunction "2_2") (pintype "passive"))
    )
    (net (code "59") (name "Net-(R44-Pad2)") (class "Default")
      (node (ref "R44") (pin "2") (pinfunction "2_2") (pintype "passive"))
      (node (ref "R45") (pin "1") (pinfunction "1_1") (pintype "passive"))
      (node (ref "R49") (pin "1") (pinfunction "1_1") (pintype "passive"))
    )
    (net (code "60") (name "Net-(R46-Pad2)") (class "Default")
      (node (ref "R46") (pin "2") (pinfunction "2_2") (pintype "passive"))
      (node (ref "R47") (pin "1") (pinfunction "1_1") (pintype "passive"))
      (node (ref "R48") (pin "1") (pinfunction "1_1") (pintype "passive"))
    )
    (net (code "61") (name "Net-(U8A-1IN+)") (class "Default")
      (node (ref "D14") (pin "3") (pinfunction "3_3") (pintype "passive"))
      (node (ref "R37") (pin "1") (pinfunction "1_1") (pintype "passive"))
      (node (ref "R39") (pin "1") (pinfunction "1_1") (pintype "passive"))
      (node (ref "U8") (pin "3") (pinfunction "1IN+_3") (pintype "input"))
    )
    (net (code "62") (name "Net-(U8A-1IN-)") (class "Default")
      (node (ref "R41") (pin "2") (pinfunction "2_2") (pintype "passive"))
      (node (ref "U8") (pin "2") (pinfunction "1IN-_2") (pintype "input"))
    )
    (net (code "63") (name "Net-(U8A-1OUT)") (class "Default")
      (node (ref "R38") (pin "1") (pinfunction "1_1") (pintype "passive"))
      (node (ref "R40") (pin "1") (pinfunction "1_1") (pintype "passive"))
      (node (ref "R41") (pin "1") (pinfunction "1_1") (pintype "passive"))
      (node (ref "U8") (pin "1") (pinfunction "1OUT_1") (pintype "output"))
    )
    (net (code "64") (name "Net-(U8B-2IN+)") (class "Default")
      (node (ref "D11") (pin "3") (pinfunction "3_3") (pintype "passive"))
      (node (ref "R24") (pin "1") (pinfunction "1_1") (pintype "passive"))
      (node (ref "R27") (pin "1") (pinfunction "1_1") (pintype "passive"))
      (node (ref "U8") (pin "5") (pinfunction "2IN+_5") (pintype "input"))
    )
    (net (code "65") (name "Net-(U8B-2IN-)") (class "Default")
      (node (ref "R29") (pin "2") (pinfunction "2_2") (pintype "passive"))
      (node (ref "U8") (pin "6") (pinfunction "2IN-_6") (pintype "input"))
    )
    (net (code "66") (name "Net-(U8B-2OUT)") (class "Default")
      (node (ref "R25") (pin "1") (pinfunction "1_1") (pintype "passive"))
      (node (ref "R28") (pin "1") (pinfunction "1_1") (pintype "passive"))
      (node (ref "R29") (pin "1") (pinfunction "1_1") (pintype "passive"))
      (node (ref "U8") (pin "7") (pinfunction "2OUT_7") (pintype "output"))
    )
    (net (code "67") (name "Net-(U10-IN+)") (class "Default")
      (node (ref "C39") (pin "2") (pinfunction "2_2") (pintype "passive"))
      (node (ref "R52") (pin "2") (pinfunction "2_2") (pintype "passive"))
      (node (ref "U10") (pin "1") (pinfunction "IN+_1") (pintype "input"))
    )
    (net (code "68") (name "Net-(U10-IN-)") (class "Default")
      (node (ref "C41") (pin "2") (pinfunction "2_2") (pintype "passive"))
      (node (ref "R55") (pin "2") (pinfunction "2_2") (pintype "passive"))
      (node (ref "R56") (pin "1") (pinfunction "1_1") (pintype "passive"))
      (node (ref "U10") (pin "3") (pinfunction "IN-_3") (pintype "input"))
    )
    (net (code "69") (name "Net-(U10-OUT)") (class "Default")
      (node (ref "C41") (pin "1") (pinfunction "1_1") (pintype "passive"))
      (node (ref "D17") (pin "3") (pinfunction "3_3") (pintype "passive"))
      (node (ref "R54") (pin "1") (pinfunction "1_1") (pintype "passive"))
      (node (ref "U10") (pin "4") (pinfunction "OUT_4") (pintype "output"))
    )
    (net (code "70") (name "VLIM") (class "Default")
      (node (ref "C34") (pin "1") (pinfunction "1_1") (pintype "passive"))
      (node (ref "C37") (pin "1") (pinfunction "1_1") (pintype "passive"))
      (node (ref "D17") (pin "2") (pinfunction "2_2") (pintype "passive"))
      (node (ref "U10") (pin "5") (pinfunction "VCC_5") (pintype "power_in"))
      (node (ref "U8") (pin "8") (pinfunction "VCC_8") (pintype "power_in"))
    )
    (net (code "71") (name "Vs_out") (class "Default")
      (node (ref "R67") (pin "1") (pinfunction "1_1") (pintype "passive"))
    )
    (net (code "72") (name "unconnected-(M1-Pad1)") (class "Default")
      (node (ref "M1") (pin "1") (pinfunction "1_1") (pintype "passive"))
    )
    (net (code "73") (name "unconnected-(M2-Pad1)") (class "Default")
      (node (ref "M2") (pin "1") (pinfunction "1_1") (pintype "passive"))
    )
    (net (code "74") (name "unconnected-(U9-UD+-Pad5)") (class "Default")
      (node (ref "U9") (pin "5") (pinfunction "UD+_5") (pintype "passive+no_connect"))
    )
    (net (code "75") (name "unconnected-(U9-UD--Pad6)") (class "Default")
      (node (ref "U9") (pin "6") (pinfunction "UD-_6") (pintype "passive+no_connect"))
    )
  )
)
